# Power_Board.net
KiCad netlist of a schematic drawn in EAGLE
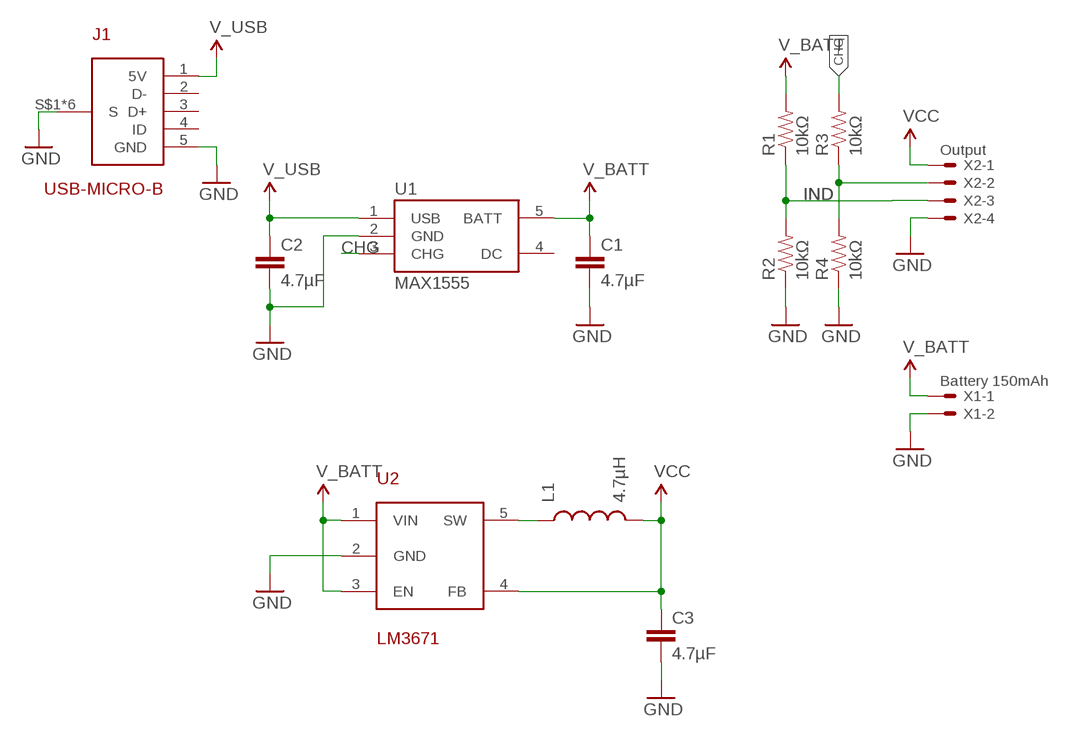
[diagram p0: schematic, sheet 1]

(export (version "E")
  (design (tool "Eeschema 10.0.6"))
  (components
    (comp (ref "C1")
      (value "4.7µF")
      (footprint "eagle-import:0805")
      (libsource (lib "eagle-import") (part "CAP0805"))
    )
    (comp (ref "C2")
      (value "4.7µF")
      (footprint "eagle-import:0805")
      (libsource (lib "eagle-import") (part "CAP0805"))
    )
    (comp (ref "C3")
      (value "4.7µF")
      (footprint "eagle-import:0805")
      (libsource (lib "eagle-import") (part "CAP0805"))
    )
    (comp (ref "J1")
      (value "USB-MICRO-B")
      (footprint "eagle-import:UB-MC5BR3")
      (libsource (lib "eagle-import") (part "USB-MICRO-B"))
    )
    (comp (ref "L1")
      (value "4.7µH")
      (footprint "eagle-import:0805")
      (libsource (lib "eagle-import") (part "INDUCTOR0805"))
    )
    (comp (ref "R1")
      (value "10kΩ")
      (footprint "eagle-import:0805")
      (libsource (lib "eagle-import") (part "RESISTOR0805-RES"))
    )
    (comp (ref "R2")
      (value "10kΩ")
      (footprint "eagle-import:0805")
      (libsource (lib "eagle-import") (part "RESISTOR0805-RES"))
    )
    (comp (ref "R3")
      (value "10kΩ")
      (footprint "eagle-import:0805")
      (libsource (lib "eagle-import") (part "RESISTOR0805-RES"))
    )
    (comp (ref "R4")
      (value "10kΩ")
      (footprint "eagle-import:0805")
      (libsource (lib "eagle-import") (part "RESISTOR0805-RES"))
    )
    (comp (ref "U1")
      (value "MAX1555")
      (footprint "eagle-import:SOT23-5")
      (libsource (lib "eagle-import") (part "MAX1555"))
    )
    (comp (ref "U2")
      (value "LM3671")
      (footprint "eagle-import:SOT23-5")
      (libsource (lib "eagle-import") (part "LM3671"))
    )
    (comp (ref "X1")
      (value "Battery 150mAh")
      (footprint "eagle-import:SM02B-SRSS-TB")
      (libsource (lib "eagle-import") (part "?M02B-SRSS-TBS"))
    )
    (comp (ref "X2")
      (value "Output")
      (footprint "eagle-import:SM04B-SRSS-TB")
      (libsource (lib "eagle-import") (part "?M04B-SRSS-TBS"))
    )
  )
  (nets
    (net (code "1") (name "/IND") (class "Default")
      (node (ref "R1") (pin "1") (pinfunction "1_1") (pintype "passive"))
      (node (ref "R2") (pin "2") (pinfunction "2_2") (pintype "passive"))
      (node (ref "X2") (pin "3") (pinfunction "S_3") (pintype "passive"))
    )
    (net (code "2") (name "CHG") (class "Default")
      (node (ref "R3") (pin "2") (pinfunction "2_2") (pintype "passive"))
      (node (ref "U1") (pin "3") (pinfunction "CHG_3") (pintype "bidirectional"))
    )
    (net (code "3") (name "GND") (class "Default")
      (node (ref "C1") (pin "2") (pinfunction "2_2") (pintype "passive"))
      (node (ref "C2") (pin "2") (pinfunction "2_2") (pintype "passive"))
      (node (ref "C3") (pin "2") (pinfunction "2_2") (pintype "passive"))
      (node (ref "J1") (pin "5") (pinfunction "GND_5") (pintype "power_in"))
      (node (ref "J1") (pin "S$1") (pinfunction "S_S$1") (pintype "bidirectional"))
      (node (ref "J1") (pin "S$2") (pinfunction "S_S$2") (pintype "bidirectional"))
      (node (ref "J1") (pin "S$3") (pinfunction "S_S$3") (pintype "bidirectional"))
      (node (ref "J1") (pin "S$4") (pinfunction "S_S$4") (pintype "bidirectional"))
      (node (ref "J1") (pin "S$5") (pinfunction "S_S$5") (pintype "bidirectional"))
      (node (ref "J1") (pin "S$6") (pinfunction "S_S$6") (pintype "bidirectional"))
      (node (ref "R2") (pin "1") (pinfunction "1_1") (pintype "passive"))
      (node (ref "R4") (pin "1") (pinfunction "1_1") (pintype "passive"))
      (node (ref "U1") (pin "2") (pinfunction "GND_2") (pintype "bidirectional"))
      (node (ref "U2") (pin "2") (pinfunction "GND_2") (pintype "bidirectional"))
      (node (ref "X1") (pin "2") (pinfunction "S_2") (pintype "passive"))
      (node (ref "X2") (pin "4") (pinfunction "S_4") (pintype "passive"))
    )
    (net (code "4") (name "Net-(U2-SW)") (class "Default")
      (node (ref "L1") (pin "1") (pinfunction "1_1") (pintype "passive"))
      (node (ref "U2") (pin "5") (pinfunction "SW_5") (pintype "bidirectional"))
    )
    (net (code "5") (name "Net-(X2B-S)") (class "Default")
      (node (ref "R3") (pin "1") (pinfunction "1_1") (pintype "passive"))
      (node (ref "R4") (pin "2") (pinfunction "2_2") (pintype "passive"))
      (node (ref "X2") (pin "2") (pinfunction "S_2") (pintype "passive"))
    )
    (net (code "6") (name "VCC") (class "Default")
      (node (ref "C3") (pin "1") (pinfunction "1_1") (pintype "passive"))
      (node (ref "L1") (pin "2") (pinfunction "2_2") (pintype "passive"))
      (node (ref "U2") (pin "4") (pinfunction "FB_4") (pintype "bidirectional"))
      (node (ref "X2") (pin "1") (pinfunction "S_1") (pintype "passive"))
    )
    (net (code "7") (name "V_BATT") (class "Default")
      (node (ref "C1") (pin "1") (pinfunction "1_1") (pintype "passive"))
      (node (ref "R1") (pin "2") (pinfunction "2_2") (pintype "passive"))
      (node (ref "U1") (pin "5") (pinfunction "BATT_5") (pintype "bidirectional"))
      (node (ref "U2") (pin "1") (pinfunction "VIN_1") (pintype "bidirectional"))
      (node (ref "U2") (pin "3") (pinfunction "EN_3") (pintype "bidirectional"))
      (node (ref "X1") (pin "1") (pinfunction "S_1") (pintype "passive"))
    )
    (net (code "8") (name "V_USB") (class "Default")
      (node (ref "C2") (pin "1") (pinfunction "1_1") (pintype "passive"))
      (node (ref "J1") (pin "1") (pinfunction "5V_1") (pintype "power_in"))
      (node (ref "U1") (pin "1") (pinfunction "USB_1") (pintype "bidirectional"))
    )
    (net (code "9") (name "unconnected-(J1-D+-Pad3)") (class "Default")
      (node (ref "J1") (pin "3") (pinfunction "D+_3") (pintype "bidirectional"))
    )
    (net (code "10") (name "unconnected-(J1-D--Pad2)") (class "Default")
      (node (ref "J1") (pin "2") (pinfunction "D-_2") (pintype "bidirectional"))
    )
    (net (code "11") (name "unconnected-(J1-ID-Pad4)") (class "Default")
      (node (ref "J1") (pin "4") (pinfunction "ID_4") (pintype "bidirectional"))
    )
    (net (code "12") (name "unconnected-(U1-DC-Pad4)") (class "Default")
      (node (ref "U1") (pin "4") (pinfunction "DC_4") (pintype "bidirectional"))
    )
  )
)
